# 2_adc.net
KiCad netlist of a schematic drawn in EAGLE
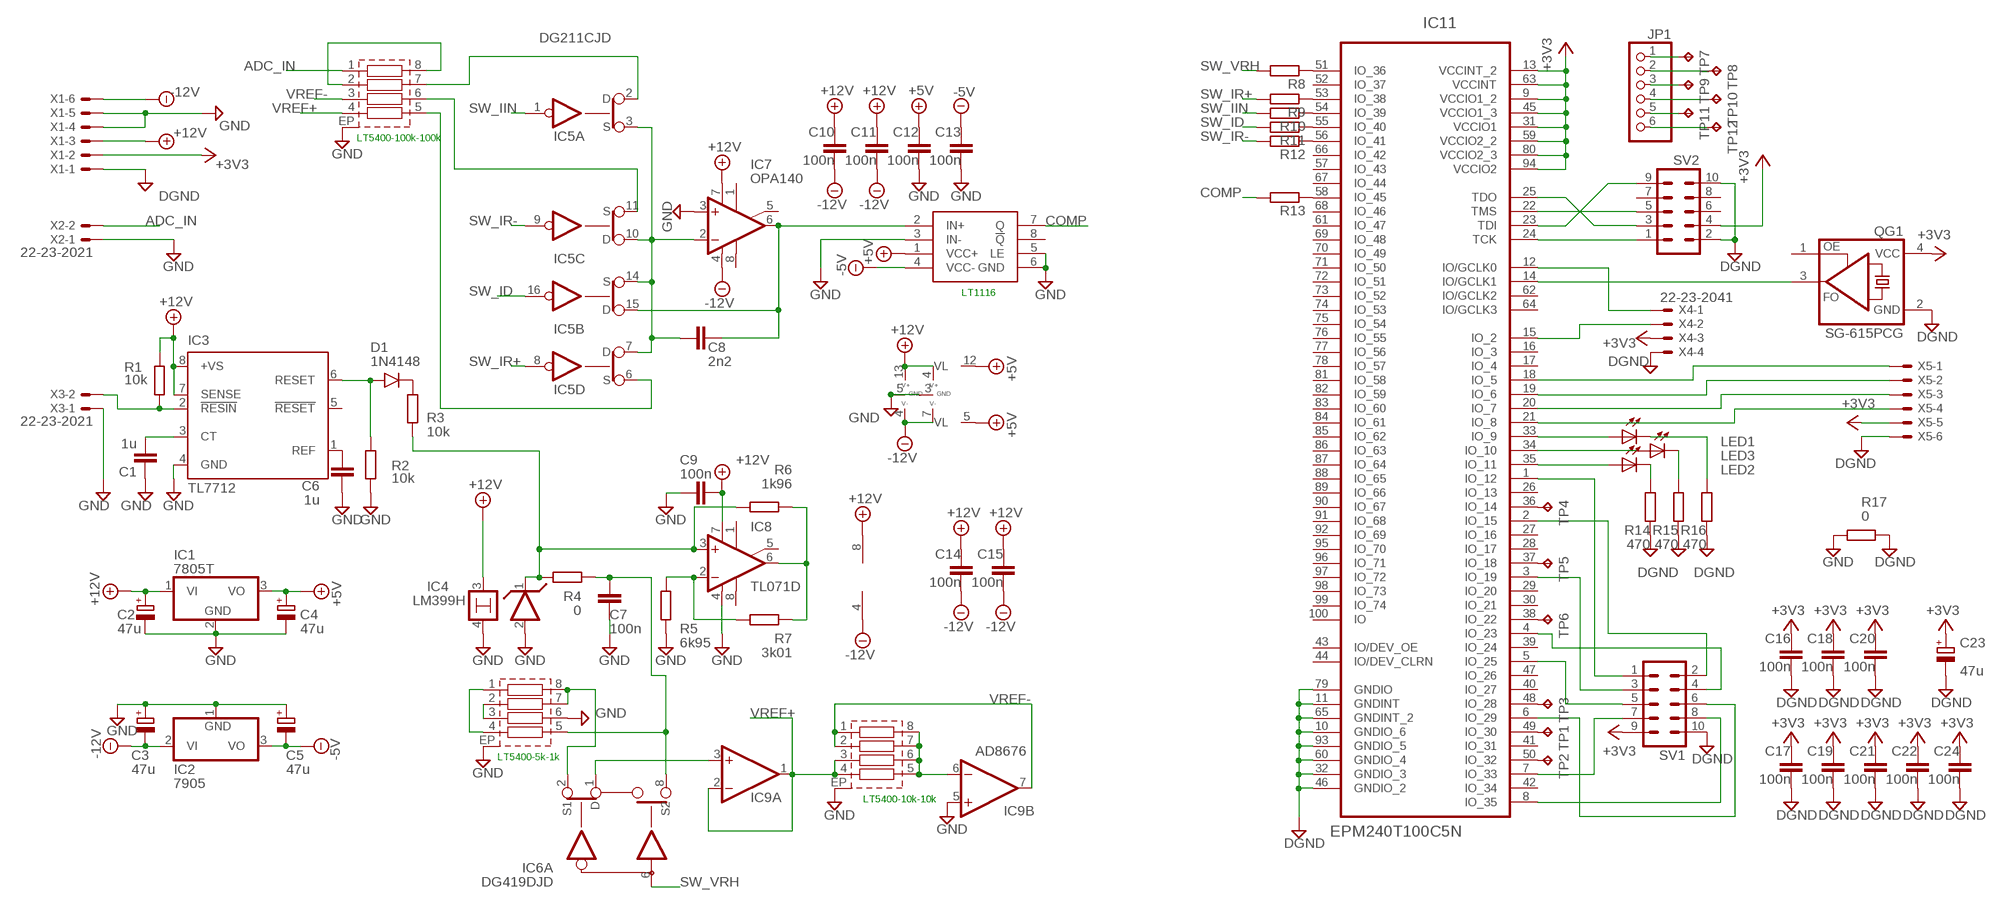
[diagram p0: schematic, sheet 1]

(export (version "E")
  (design (tool "Eeschema 10.0.6"))
  (components
    (comp (ref "C1")
      (value "1u")
      (footprint "eagle-import:R0805")
      (libsource (lib "eagle-import") (part "C_0806"))
    )
    (comp (ref "C2")
      (value "47u")
      (footprint "eagle-import:SMC_C")
      (libsource (lib "eagle-import") (part "CPOL-EUSMCC"))
    )
    (comp (ref "C3")
      (value "47u")
      (footprint "eagle-import:SMC_C")
      (libsource (lib "eagle-import") (part "CPOL-EUSMCC"))
    )
    (comp (ref "C4")
      (value "47u")
      (footprint "eagle-import:SMC_C")
      (libsource (lib "eagle-import") (part "CPOL-EUSMCC"))
    )
    (comp (ref "C5")
      (value "47u")
      (footprint "eagle-import:SMC_C")
      (libsource (lib "eagle-import") (part "CPOL-EUSMCC"))
    )
    (comp (ref "C6")
      (value "1u")
      (footprint "eagle-import:R0805")
      (libsource (lib "eagle-import") (part "C_0806"))
    )
    (comp (ref "C7")
      (value "100n")
      (footprint "eagle-import:C050-035X075")
      (libsource (lib "eagle-import") (part "C-EU050-035X075"))
    )
    (comp (ref "C8")
      (value "2n2")
      (footprint "eagle-import:C150-054X183")
      (libsource (lib "eagle-import") (part "C-EU150-054X183"))
    )
    (comp (ref "C9")
      (value "100n")
      (footprint "eagle-import:R0805")
      (libsource (lib "eagle-import") (part "C_0806"))
    )
    (comp (ref "C10")
      (value "100n")
      (footprint "eagle-import:R0805")
      (libsource (lib "eagle-import") (part "C_0806"))
    )
    (comp (ref "C11")
      (value "100n")
      (footprint "eagle-import:R0805")
      (libsource (lib "eagle-import") (part "C_0806"))
    )
    (comp (ref "C12")
      (value "100n")
      (footprint "eagle-import:R0805")
      (libsource (lib "eagle-import") (part "C_0806"))
    )
    (comp (ref "C13")
      (value "100n")
      (footprint "eagle-import:R0805")
      (libsource (lib "eagle-import") (part "C_0806"))
    )
    (comp (ref "C14")
      (value "100n")
      (footprint "eagle-import:R0805")
      (libsource (lib "eagle-import") (part "C_0806"))
    )
    (comp (ref "C15")
      (value "100n")
      (footprint "eagle-import:R0805")
      (libsource (lib "eagle-import") (part "C_0806"))
    )
    (comp (ref "C16")
      (value "100n")
      (footprint "eagle-import:R0805")
      (libsource (lib "eagle-import") (part "C_0806"))
    )
    (comp (ref "C17")
      (value "100n")
      (footprint "eagle-import:R0805")
      (libsource (lib "eagle-import") (part "C_0806"))
    )
    (comp (ref "C18")
      (value "100n")
      (footprint "eagle-import:R0805")
      (libsource (lib "eagle-import") (part "C_0806"))
    )
    (comp (ref "C19")
      (value "100n")
      (footprint "eagle-import:R0805")
      (libsource (lib "eagle-import") (part "C_0806"))
    )
    (comp (ref "C20")
      (value "100n")
      (footprint "eagle-import:R0805")
      (libsource (lib "eagle-import") (part "C_0806"))
    )
    (comp (ref "C21")
      (value "100n")
      (footprint "eagle-import:R0805")
      (libsource (lib "eagle-import") (part "C_0806"))
    )
    (comp (ref "C22")
      (value "100n")
      (footprint "eagle-import:R0805")
      (libsource (lib "eagle-import") (part "C_0806"))
    )
    (comp (ref "C23")
      (value "47u")
      (footprint "eagle-import:SMC_C")
      (libsource (lib "eagle-import") (part "CPOL-EUSMCC"))
    )
    (comp (ref "C24")
      (value "100n")
      (footprint "eagle-import:R0805")
      (libsource (lib "eagle-import") (part "C_0806"))
    )
    (comp (ref "D1")
      (value "1N4148")
      (footprint "eagle-import:SOD-80")
      (libsource (lib "eagle-import") (part "1N4148SOD"))
    )
    (comp (ref "IC1")
      (value "7805T")
      (footprint "eagle-import:TO220H")
      (libsource (lib "eagle-import") (part "78T05"))
    )
    (comp (ref "IC2")
      (value "7905")
      (footprint "eagle-import:TO220H")
      (libsource (lib "eagle-import") (part "79T05"))
    )
    (comp (ref "IC3")
      (value "TL7712")
      (footprint "eagle-import:SO08")
      (libsource (lib "eagle-import") (part "TL770D05AI"))
    )
    (comp (ref "IC4")
      (value "LM399H")
      (footprint "eagle-import:TO39_4")
      (libsource (lib "eagle-import") (part "LM399H"))
    )
    (comp (ref "IC5")
      (value "DG211CJD")
      (footprint "eagle-import:SO16")
      (libsource (lib "eagle-import") (part "DG211CJD"))
    )
    (comp (ref "IC6")
      (value "DG419DJD")
      (footprint "eagle-import:SO08")
      (libsource (lib "eagle-import") (part "DG419DJD"))
    )
    (comp (ref "IC7")
      (value "OPA140")
      (footprint "eagle-import:SO08")
      (libsource (lib "eagle-import") (part "TL071D"))
    )
    (comp (ref "IC8")
      (value "TL071D")
      (footprint "eagle-import:SO08")
      (libsource (lib "eagle-import") (part "TL071D"))
    )
    (comp (ref "IC9")
      (value "AD8676")
      (footprint "eagle-import:SO08")
      (libsource (lib "eagle-import") (part "TL072D"))
    )
    (comp (ref "IC10")
      (value "LT1116")
      (footprint "eagle-import:SO-08")
      (libsource (lib "eagle-import") (part "LT1116"))
    )
    (comp (ref "IC11")
      (value "EPM240T100C5N")
      (footprint "eagle-import:QFP50P1600X1600X120-100N")
      (libsource (lib "eagle-import") (part "EPM240T100C5N"))
    )
    (comp (ref "JP1")
      (value "PINHD-1X06_2.54")
      (footprint "eagle-import:1X06")
      (libsource (lib "eagle-import") (part "PINHD-1X06_2.54"))
    )
    (comp (ref "LED1")
      (value "LEDCHIPLED_0805")
      (footprint "eagle-import:CHIPLED_0805")
      (libsource (lib "eagle-import") (part "LEDCHIPLED_0805"))
    )
    (comp (ref "LED2")
      (value "LEDCHIPLED_0805")
      (footprint "eagle-import:CHIPLED_0805")
      (libsource (lib "eagle-import") (part "LEDCHIPLED_0805"))
    )
    (comp (ref "LED3")
      (value "LEDCHIPLED_0805")
      (footprint "eagle-import:CHIPLED_0805")
      (libsource (lib "eagle-import") (part "LEDCHIPLED_0805"))
    )
    (comp (ref "QG1")
      (value "SG-615PCG")
      (footprint "eagle-import:SG-615")
      (libsource (lib "eagle-import") (part "SG-615PCG"))
    )
    (comp (ref "R1")
      (value "10k")
      (footprint "eagle-import:R0805")
      (libsource (lib "eagle-import") (part "R_0805"))
    )
    (comp (ref "R2")
      (value "10k")
      (footprint "eagle-import:R0805")
      (libsource (lib "eagle-import") (part "R_0805"))
    )
    (comp (ref "R3")
      (value "10k")
      (footprint "eagle-import:R0805")
      (libsource (lib "eagle-import") (part "R_0805"))
    )
    (comp (ref "R4")
      (value "0")
      (footprint "eagle-import:R_TR191")
      (libsource (lib "eagle-import") (part "R191"))
    )
    (comp (ref "R5")
      (value "6k95")
      (footprint "eagle-import:R_TR191")
      (libsource (lib "eagle-import") (part "R191"))
    )
    (comp (ref "R6")
      (value "1k96")
      (footprint "eagle-import:R_TR191")
      (libsource (lib "eagle-import") (part "R191"))
    )
    (comp (ref "R7")
      (value "3k01")
      (footprint "eagle-import:R_TR191")
      (libsource (lib "eagle-import") (part "R191"))
    )
    (comp (ref "R8")
      (value "R_0805")
      (footprint "eagle-import:R0805")
      (libsource (lib "eagle-import") (part "R_0805"))
    )
    (comp (ref "R9")
      (value "R_0805")
      (footprint "eagle-import:R0805")
      (libsource (lib "eagle-import") (part "R_0805"))
    )
    (comp (ref "R10")
      (value "R_0805")
      (footprint "eagle-import:R0805")
      (libsource (lib "eagle-import") (part "R_0805"))
    )
    (comp (ref "R11")
      (value "R_0805")
      (footprint "eagle-import:R0805")
      (libsource (lib "eagle-import") (part "R_0805"))
    )
    (comp (ref "R12")
      (value "R_0805")
      (footprint "eagle-import:R0805")
      (libsource (lib "eagle-import") (part "R_0805"))
    )
    (comp (ref "R13")
      (value "R_0805")
      (footprint "eagle-import:R0805")
      (libsource (lib "eagle-import") (part "R_0805"))
    )
    (comp (ref "R14")
      (value "470")
      (footprint "eagle-import:R0805")
      (libsource (lib "eagle-import") (part "R_0805"))
    )
    (comp (ref "R15")
      (value "470")
      (footprint "eagle-import:R0805")
      (libsource (lib "eagle-import") (part "R_0805"))
    )
    (comp (ref "R16")
      (value "470")
      (footprint "eagle-import:R0805")
      (libsource (lib "eagle-import") (part "R_0805"))
    )
    (comp (ref "R17")
      (value "0")
      (footprint "eagle-import:R0805")
      (libsource (lib "eagle-import") (part "R_0805"))
    )
    (comp (ref "SV1")
      (value "ML10")
      (footprint "eagle-import:ML10")
      (libsource (lib "eagle-import") (part "ML10"))
    )
    (comp (ref "SV2")
      (value "ML10")
      (footprint "eagle-import:ML10")
      (libsource (lib "eagle-import") (part "ML10"))
    )
    (comp (ref "TP1")
      (value "TPB1,27")
      (footprint "eagle-import:B1,27")
      (libsource (lib "eagle-import") (part "TPB1,27"))
    )
    (comp (ref "TP2")
      (value "TPB1,27")
      (footprint "eagle-import:B1,27")
      (libsource (lib "eagle-import") (part "TPB1,27"))
    )
    (comp (ref "TP3")
      (value "TPB1,27")
      (footprint "eagle-import:B1,27")
      (libsource (lib "eagle-import") (part "TPB1,27"))
    )
    (comp (ref "TP4")
      (value "TPB1,27")
      (footprint "eagle-import:B1,27")
      (libsource (lib "eagle-import") (part "TPB1,27"))
    )
    (comp (ref "TP5")
      (value "TPB1,27")
      (footprint "eagle-import:B1,27")
      (libsource (lib "eagle-import") (part "TPB1,27"))
    )
    (comp (ref "TP6")
      (value "TPB1,27")
      (footprint "eagle-import:B1,27")
      (libsource (lib "eagle-import") (part "TPB1,27"))
    )
    (comp (ref "TP7")
      (value "TPB1,27")
      (footprint "eagle-import:B1,27")
      (libsource (lib "eagle-import") (part "TPB1,27"))
    )
    (comp (ref "TP8")
      (value "TPB1,27")
      (footprint "eagle-import:B1,27")
      (libsource (lib "eagle-import") (part "TPB1,27"))
    )
    (comp (ref "TP9")
      (value "TPB1,27")
      (footprint "eagle-import:B1,27")
      (libsource (lib "eagle-import") (part "TPB1,27"))
    )
    (comp (ref "TP10")
      (value "TPB1,27")
      (footprint "eagle-import:B1,27")
      (libsource (lib "eagle-import") (part "TPB1,27"))
    )
    (comp (ref "TP11")
      (value "TPB1,27")
      (footprint "eagle-import:B1,27")
      (libsource (lib "eagle-import") (part "TPB1,27"))
    )
    (comp (ref "TP12")
      (value "TPB1,27")
      (footprint "eagle-import:B1,27")
      (libsource (lib "eagle-import") (part "TPB1,27"))
    )
    (comp (ref "U$1")
      (value "LT5400-100k-100k")
      (footprint "eagle-import:MSOP8-EP")
      (libsource (lib "eagle-import") (part "LT5400"))
    )
    (comp (ref "U$2")
      (value "LT5400-5k-1k")
      (footprint "eagle-import:MSOP8-EP")
      (libsource (lib "eagle-import") (part "LT5400"))
    )
    (comp (ref "U$3")
      (value "LT5400-10k+10k")
      (footprint "eagle-import:MSOP8-EP")
      (libsource (lib "eagle-import") (part "LT5400"))
    )
    (comp (ref "X1")
      (value "22-23-2061")
      (footprint "eagle-import:22-23-2061")
      (fields (field (name "MF") "MOLEX"))
      (libsource (lib "eagle-import") (part "22-23-2061"))
    )
    (comp (ref "X2")
      (value "22-23-2021")
      (footprint "eagle-import:22-23-2021")
      (fields (field (name "MF") "MOLEX"))
      (libsource (lib "eagle-import") (part "22-23-2021"))
    )
    (comp (ref "X3")
      (value "22-23-2021")
      (footprint "eagle-import:22-23-2021")
      (fields (field (name "MF") "MOLEX"))
      (libsource (lib "eagle-import") (part "22-23-2021"))
    )
    (comp (ref "X4")
      (value "22-23-2041")
      (footprint "eagle-import:22-23-2041")
      (fields (field (name "MF") "MOLEX"))
      (libsource (lib "eagle-import") (part "22-23-2041"))
    )
    (comp (ref "X5")
      (value "22-23-2061")
      (footprint "eagle-import:22-23-2061")
      (fields (field (name "MF") "MOLEX"))
      (libsource (lib "eagle-import") (part "22-23-2061"))
    )
  )
  (nets
    (net (code "1") (name "+3V3") (class "Default")
      (node (ref "C16") (pin "2") (pinfunction "2_2") (pintype "passive"))
      (node (ref "C17") (pin "2") (pinfunction "2_2") (pintype "passive"))
      (node (ref "C18") (pin "2") (pinfunction "2_2") (pintype "passive"))
      (node (ref "C19") (pin "2") (pinfunction "2_2") (pintype "passive"))
      (node (ref "C20") (pin "2") (pinfunction "2_2") (pintype "passive"))
      (node (ref "C21") (pin "2") (pinfunction "2_2") (pintype "passive"))
      (node (ref "C22") (pin "2") (pinfunction "2_2") (pintype "passive"))
      (node (ref "C23") (pin "+") (pinfunction "+_+") (pintype "passive"))
      (node (ref "C24") (pin "2") (pinfunction "2_2") (pintype "passive"))
      (node (ref "IC11") (pin "13") (pinfunction "VCCINT_2_13") (pintype "power_in"))
      (node (ref "IC11") (pin "31") (pinfunction "VCCIO1_31") (pintype "power_in"))
      (node (ref "IC11") (pin "45") (pinfunction "VCCIO1_3_45") (pintype "power_in"))
      (node (ref "IC11") (pin "59") (pinfunction "VCCIO2_2_59") (pintype "power_in"))
      (node (ref "IC11") (pin "63") (pinfunction "VCCINT_63") (pintype "power_in"))
      (node (ref "IC11") (pin "80") (pinfunction "VCCIO2_3_80") (pintype "power_in"))
      (node (ref "IC11") (pin "9") (pinfunction "VCCIO1_2_9") (pintype "power_in"))
      (node (ref "IC11") (pin "94") (pinfunction "VCCIO2_94") (pintype "power_in"))
      (node (ref "QG1") (pin "4") (pinfunction "VCC_4") (pintype "power_in"))
      (node (ref "SV1") (pin "9") (pinfunction "9_9") (pintype "passive"))
      (node (ref "SV2") (pin "4") (pinfunction "4_4") (pintype "passive"))
      (node (ref "X1") (pin "2") (pinfunction "S_2") (pintype "passive"))
      (node (ref "X4") (pin "3") (pinfunction "S_3") (pintype "passive"))
      (node (ref "X5") (pin "5") (pinfunction "S_5") (pintype "passive"))
    )
    (net (code "2") (name "+5V") (class "Default")
      (node (ref "C12") (pin "2") (pinfunction "2_2") (pintype "passive"))
      (node (ref "C4") (pin "+") (pinfunction "+_+") (pintype "passive"))
      (node (ref "IC1") (pin "3") (pinfunction "VO_3") (pintype "passive"))
      (node (ref "IC10") (pin "1") (pinfunction "VCC+_1") (pintype "bidirectional"))
      (node (ref "IC5") (pin "12") (pinfunction "VL_12") (pintype "input"))
      (node (ref "IC6") (pin "5") (pinfunction "VL_5") (pintype "input"))
    )
    (net (code "3") (name "+12V") (class "Default")
      (node (ref "C10") (pin "2") (pinfunction "2_2") (pintype "passive"))
      (node (ref "C11") (pin "2") (pinfunction "2_2") (pintype "passive"))
      (node (ref "C14") (pin "2") (pinfunction "2_2") (pintype "passive"))
      (node (ref "C15") (pin "2") (pinfunction "2_2") (pintype "passive"))
      (node (ref "C2") (pin "+") (pinfunction "+_+") (pintype "passive"))
      (node (ref "C9") (pin "2") (pinfunction "2_2") (pintype "passive"))
      (node (ref "IC1") (pin "1") (pinfunction "VI_1") (pintype "input"))
      (node (ref "IC3") (pin "7") (pinfunction "SENSE_7") (pintype "input"))
      (node (ref "IC3") (pin "8") (pinfunction "+VS_8") (pintype "input"))
      (node (ref "IC4") (pin "3") (pinfunction "3_3") (pintype "input"))
      (node (ref "IC5") (pin "13") (pinfunction "V+_13") (pintype "power_in"))
      (node (ref "IC6") (pin "4") (pinfunction "V+_4") (pintype "power_in"))
      (node (ref "IC7") (pin "7") (pinfunction "V+_7") (pintype "power_in"))
      (node (ref "IC8") (pin "7") (pinfunction "V+_7") (pintype "power_in"))
      (node (ref "IC9") (pin "8") (pinfunction "V+_8") (pintype "power_in"))
      (node (ref "R1") (pin "2") (pinfunction "2_2") (pintype "passive"))
      (node (ref "X1") (pin "3") (pinfunction "S_3") (pintype "passive"))
    )
    (net (code "4") (name "-5V") (class "Default")
      (node (ref "C13") (pin "2") (pinfunction "2_2") (pintype "passive"))
      (node (ref "C5") (pin "-") (pinfunction "-_-") (pintype "passive"))
      (node (ref "IC10") (pin "4") (pinfunction "VCC-_4") (pintype "bidirectional"))
      (node (ref "IC2") (pin "3") (pinfunction "VO_3") (pintype "passive"))
    )
    (net (code "5") (name "-12V") (class "Default")
      (node (ref "C10") (pin "1") (pinfunction "1_1") (pintype "passive"))
      (node (ref "C11") (pin "1") (pinfunction "1_1") (pintype "passive"))
      (node (ref "C14") (pin "1") (pinfunction "1_1") (pintype "passive"))
      (node (ref "C15") (pin "1") (pinfunction "1_1") (pintype "passive"))
      (node (ref "C3") (pin "-") (pinfunction "-_-") (pintype "passive"))
      (node (ref "IC2") (pin "2") (pinfunction "VI_2") (pintype "input"))
      (node (ref "IC5") (pin "4") (pinfunction "V-_4") (pintype "power_in"))
      (node (ref "IC6") (pin "7") (pinfunction "V-_7") (pintype "power_in"))
      (node (ref "IC7") (pin "4") (pinfunction "V-_4") (pintype "power_in"))
      (node (ref "IC9") (pin "4") (pinfunction "V-_4") (pintype "power_in"))
      (node (ref "X1") (pin "6") (pinfunction "S_6") (pintype "passive"))
    )
    (net (code "6") (name "/ADC_IN") (class "Default")
      (node (ref "U$1") (pin "1") (pinfunction "R1A_1") (pintype "bidirectional"))
      (node (ref "X2") (pin "2") (pinfunction "S_2") (pintype "passive"))
    )
    (net (code "7") (name "/COMP") (class "Default")
      (node (ref "IC10") (pin "7") (pinfunction "Q_7") (pintype "bidirectional"))
      (node (ref "R13") (pin "2") (pinfunction "2_2") (pintype "passive"))
    )
    (net (code "8") (name "/SW_ID") (class "Default")
      (node (ref "IC5") (pin "16") (pinfunction "IN_16") (pintype "input"))
      (node (ref "R11") (pin "2") (pinfunction "2_2") (pintype "passive"))
    )
    (net (code "9") (name "/SW_IIN") (class "Default")
      (node (ref "IC5") (pin "1") (pinfunction "IN_1") (pintype "input"))
      (node (ref "R10") (pin "2") (pinfunction "2_2") (pintype "passive"))
    )
    (net (code "10") (name "/SW_IR+") (class "Default")
      (node (ref "IC5") (pin "8") (pinfunction "IN_8") (pintype "input"))
      (node (ref "R9") (pin "2") (pinfunction "2_2") (pintype "passive"))
    )
    (net (code "11") (name "/SW_IR-") (class "Default")
      (node (ref "IC5") (pin "9") (pinfunction "IN_9") (pintype "input"))
      (node (ref "R12") (pin "2") (pinfunction "2_2") (pintype "passive"))
    )
    (net (code "12") (name "/SW_VRH") (class "Default")
      (node (ref "IC6") (pin "6") (pinfunction "IN_6") (pintype "input"))
      (node (ref "R8") (pin "2") (pinfunction "2_2") (pintype "passive"))
    )
    (net (code "13") (name "/VREF+") (class "Default")
      (node (ref "IC9") (pin "1") (pinfunction "OUT_1") (pintype "output"))
      (node (ref "IC9") (pin "2") (pinfunction "-IN_2") (pintype "input"))
      (node (ref "U$1") (pin "4") (pinfunction "R4A_4") (pintype "bidirectional"))
      (node (ref "U$3") (pin "3") (pinfunction "R3A_3") (pintype "bidirectional"))
      (node (ref "U$3") (pin "4") (pinfunction "R4A_4") (pintype "bidirectional"))
    )
    (net (code "14") (name "/VREF-") (class "Default")
      (node (ref "IC9") (pin "7") (pinfunction "OUT_7") (pintype "output"))
      (node (ref "U$1") (pin "3") (pinfunction "R3A_3") (pintype "bidirectional"))
      (node (ref "U$3") (pin "1") (pinfunction "R1A_1") (pintype "bidirectional"))
      (node (ref "U$3") (pin "2") (pinfunction "R2A_2") (pintype "bidirectional"))
    )
    (net (code "15") (name "DGND") (class "Default")
      (node (ref "C16") (pin "1") (pinfunction "1_1") (pintype "passive"))
      (node (ref "C17") (pin "1") (pinfunction "1_1") (pintype "passive"))
      (node (ref "C18") (pin "1") (pinfunction "1_1") (pintype "passive"))
      (node (ref "C19") (pin "1") (pinfunction "1_1") (pintype "passive"))
      (node (ref "C20") (pin "1") (pinfunction "1_1") (pintype "passive"))
      (node (ref "C21") (pin "1") (pinfunction "1_1") (pintype "passive"))
      (node (ref "C22") (pin "1") (pinfunction "1_1") (pintype "passive"))
      (node (ref "C23") (pin "-") (pinfunction "-_-") (pintype "passive"))
      (node (ref "C24") (pin "1") (pinfunction "1_1") (pintype "passive"))
      (node (ref "IC11") (pin "10") (pinfunction "GNDIO_6_10") (pintype "passive"))
      (node (ref "IC11") (pin "11") (pinfunction "GNDINT_11") (pintype "passive"))
      (node (ref "IC11") (pin "32") (pinfunction "GNDIO_3_32") (pintype "passive"))
      (node (ref "IC11") (pin "46") (pinfunction "GNDIO_2_46") (pintype "passive"))
      (node (ref "IC11") (pin "60") (pinfunction "GNDIO_4_60") (pintype "passive"))
      (node (ref "IC11") (pin "65") (pinfunction "GNDINT_2_65") (pintype "passive"))
      (node (ref "IC11") (pin "79") (pinfunction "GNDIO_79") (pintype "passive"))
      (node (ref "IC11") (pin "93") (pinfunction "GNDIO_5_93") (pintype "passive"))
      (node (ref "QG1") (pin "2") (pinfunction "GND_2") (pintype "power_in"))
      (node (ref "R14") (pin "2") (pinfunction "2_2") (pintype "passive"))
      (node (ref "R15") (pin "2") (pinfunction "2_2") (pintype "passive"))
      (node (ref "R16") (pin "2") (pinfunction "2_2") (pintype "passive"))
      (node (ref "R17") (pin "2") (pinfunction "2_2") (pintype "passive"))
      (node (ref "SV1") (pin "10") (pinfunction "10_10") (pintype "passive"))
      (node (ref "SV2") (pin "10") (pinfunction "10_10") (pintype "passive"))
      (node (ref "SV2") (pin "2") (pinfunction "2_2") (pintype "passive"))
      (node (ref "X1") (pin "1") (pinfunction "S_1") (pintype "passive"))
      (node (ref "X4") (pin "4") (pinfunction "S_4") (pintype "passive"))
      (node (ref "X5") (pin "6") (pinfunction "S_6") (pintype "passive"))
    )
    (net (code "16") (name "GND") (class "Default")
      (node (ref "C1") (pin "1") (pinfunction "1_1") (pintype "passive"))
      (node (ref "C12") (pin "1") (pinfunction "1_1") (pintype "passive"))
      (node (ref "C13") (pin "1") (pinfunction "1_1") (pintype "passive"))
      (node (ref "C2") (pin "-") (pinfunction "-_-") (pintype "passive"))
      (node (ref "C3") (pin "+") (pinfunction "+_+") (pintype "passive"))
      (node (ref "C4") (pin "-") (pinfunction "-_-") (pintype "passive"))
      (node (ref "C5") (pin "+") (pinfunction "+_+") (pintype "passive"))
      (node (ref "C6") (pin "1") (pinfunction "1_1") (pintype "passive"))
      (node (ref "C7") (pin "2") (pinfunction "2_2") (pintype "passive"))
      (node (ref "C9") (pin "1") (pinfunction "1_1") (pintype "passive"))
      (node (ref "IC1") (pin "2") (pinfunction "GND_2") (pintype "passive"))
      (node (ref "IC10") (pin "3") (pinfunction "IN-_3") (pintype "bidirectional"))
      (node (ref "IC10") (pin "5") (pinfunction "LE_5") (pintype "bidirectional"))
      (node (ref "IC10") (pin "6") (pinfunction "GND_6") (pintype "bidirectional"))
      (node (ref "IC2") (pin "1") (pinfunction "GND_1") (pintype "passive"))
      (node (ref "IC3") (pin "4") (pinfunction "GND_4") (pintype "power_in"))
      (node (ref "IC4") (pin "2") (pinfunction "2_2") (pintype "input"))
      (node (ref "IC4") (pin "4") (pinfunction "4_4") (pintype "input"))
      (node (ref "IC5") (pin "5") (pinfunction "GND_5") (pintype "power_in"))
      (node (ref "IC6") (pin "3") (pinfunction "GND_3") (pintype "power_in"))
      (node (ref "IC7") (pin "3") (pinfunction "+IN_3") (pintype "input"))
      (node (ref "IC8") (pin "4") (pinfunction "V-_4") (pintype "power_in"))
      (node (ref "IC9") (pin "5") (pinfunction "+IN_5") (pintype "input"))
      (node (ref "R17") (pin "1") (pinfunction "1_1") (pintype "passive"))
      (node (ref "R2") (pin "1") (pinfunction "1_1") (pintype "passive"))
      (node (ref "R5") (pin "P$1") (pinfunction "1_P$1") (pintype "passive"))
      (node (ref "U$1") (pin "EP") (pinfunction "SH_EP") (pintype "bidirectional"))
      (node (ref "U$2") (pin "6") (pinfunction "R3B_6") (pintype "bidirectional"))
      (node (ref "U$2") (pin "EP") (pinfunction "SH_EP") (pintype "bidirectional"))
      (node (ref "U$3") (pin "EP") (pinfunction "SH_EP") (pintype "bidirectional"))
      (node (ref "X1") (pin "4") (pinfunction "S_4") (pintype "passive"))
      (node (ref "X1") (pin "5") (pinfunction "S_5") (pintype "passive"))
      (node (ref "X2") (pin "1") (pinfunction "S_1") (pintype "passive"))
      (node (ref "X3") (pin "1") (pinfunction "S_1") (pintype "passive"))
    )
    (net (code "17") (name "Net-(D1-PadK)") (class "Default")
      (node (ref "D1") (pin "K") (pinfunction "K_K") (pintype "output"))
      (node (ref "R3") (pin "2") (pinfunction "2_2") (pintype "passive"))
    )
    (net (code "18") (name "Net-(IC3-CT)") (class "Default")
      (node (ref "C1") (pin "2") (pinfunction "2_2") (pintype "passive"))
      (node (ref "IC3") (pin "3") (pinfunction "CT_3") (pintype "input"))
    )
    (net (code "19") (name "Net-(IC3-REF)") (class "Default")
      (node (ref "C6") (pin "2") (pinfunction "2_2") (pintype "passive"))
      (node (ref "IC3") (pin "1") (pinfunction "REF_1") (pintype "input"))
    )
    (net (code "20") (name "Net-(IC3-RESET)") (class "Default")
      (node (ref "D1") (pin "A") (pinfunction "A_A") (pintype "input"))
      (node (ref "IC3") (pin "6") (pinfunction "RESET_6") (pintype "open_collector"))
      (node (ref "R2") (pin "2") (pinfunction "2_2") (pintype "passive"))
    )
    (net (code "21") (name "Net-(IC3-~{RESIN})") (class "Default")
      (node (ref "IC3") (pin "2") (pinfunction "~{RESIN}_2") (pintype "input"))
      (node (ref "R1") (pin "1") (pinfunction "1_1") (pintype "passive"))
      (node (ref "X3") (pin "2") (pinfunction "S_2") (pintype "passive"))
    )
    (net (code "22") (name "Net-(IC5A-D)") (class "Default")
      (node (ref "IC5") (pin "2") (pinfunction "D_2") (pintype "bidirectional"))
      (node (ref "U$1") (pin "7") (pinfunction "R2B_7") (pintype "bidirectional"))
    )
    (net (code "23") (name "Net-(IC5A-S)") (class "Default")
      (node (ref "C8") (pin "1") (pinfunction "1_1") (pintype "passive"))
      (node (ref "IC5") (pin "10") (pinfunction "D_10") (pintype "bidirectional"))
      (node (ref "IC5") (pin "14") (pinfunction "S_14") (pintype "bidirectional"))
      (node (ref "IC5") (pin "3") (pinfunction "S_3") (pintype "bidirectional"))
      (node (ref "IC5") (pin "7") (pinfunction "D_7") (pintype "bidirectional"))
      (node (ref "IC7") (pin "2") (pinfunction "-IN_2") (pintype "input"))
    )
    (net (code "24") (name "Net-(IC5C-S)") (class "Default")
      (node (ref "IC5") (pin "11") (pinfunction "S_11") (pintype "bidirectional"))
      (node (ref "U$1") (pin "6") (pinfunction "R3B_6") (pintype "bidirectional"))
    )
    (net (code "25") (name "Net-(IC5D-S)") (class "Default")
      (node (ref "IC5") (pin "6") (pinfunction "S_6") (pintype "bidirectional"))
      (node (ref "U$1") (pin "5") (pinfunction "R4B_5") (pintype "bidirectional"))
    )
    (net (code "26") (name "Net-(IC6A-D)") (class "Default")
      (node (ref "IC6") (pin "1") (pinfunction "D_1") (pintype "bidirectional"))
      (node (ref "IC9") (pin "3") (pinfunction "+IN_3") (pintype "input"))
    )
    (net (code "27") (name "Net-(IC6A-S1)") (class "Default")
      (node (ref "IC6") (pin "2") (pinfunction "S1_2") (pintype "bidirectional"))
      (node (ref "U$2") (pin "7") (pinfunction "R2B_7") (pintype "bidirectional"))
      (node (ref "U$2") (pin "8") (pinfunction "R1B_8") (pintype "bidirectional"))
    )
    (net (code "28") (name "Net-(IC6A-S2)") (class "Default")
      (node (ref "C7") (pin "1") (pinfunction "1_1") (pintype "passive"))
      (node (ref "IC6") (pin "8") (pinfunction "S2_8") (pintype "bidirectional"))
      (node (ref "R4") (pin "P$1") (pinfunction "1_P$1") (pintype "passive"))
      (node (ref "U$2") (pin "5") (pinfunction "R4B_5") (pintype "bidirectional"))
    )
    (net (code "29") (name "Net-(IC8-+IN)") (class "Default")
      (node (ref "IC4") (pin "1") (pinfunction "1_1") (pintype "input"))
      (node (ref "IC8") (pin "3") (pinfunction "+IN_3") (pintype "input"))
      (node (ref "R3") (pin "1") (pinfunction "1_1") (pintype "passive"))
      (node (ref "R4") (pin "P$2") (pinfunction "2_P$2") (pintype "passive"))
      (node (ref "R6") (pin "P$2") (pinfunction "2_P$2") (pintype "passive"))
    )
    (net (code "30") (name "Net-(IC8--IN)") (class "Default")
      (node (ref "IC8") (pin "2") (pinfunction "-IN_2") (pintype "input"))
      (node (ref "R5") (pin "P$2") (pinfunction "2_P$2") (pintype "passive"))
      (node (ref "R7") (pin "P$2") (pinfunction "2_P$2") (pintype "passive"))
    )
    (net (code "31") (name "Net-(IC8-OUT)") (class "Default")
      (node (ref "IC8") (pin "6") (pinfunction "OUT_6") (pintype "output"))
      (node (ref "R6") (pin "P$1") (pinfunction "1_P$1") (pintype "passive"))
      (node (ref "R7") (pin "P$1") (pinfunction "1_P$1") (pintype "passive"))
    )
    (net (code "32") (name "Net-(IC9B--IN)") (class "Default")
      (node (ref "IC9") (pin "6") (pinfunction "-IN_6") (pintype "input"))
      (node (ref "U$3") (pin "5") (pinfunction "R4B_5") (pintype "bidirectional"))
      (node (ref "U$3") (pin "6") (pinfunction "R3B_6") (pintype "bidirectional"))
      (node (ref "U$3") (pin "7") (pinfunction "R2B_7") (pintype "bidirectional"))
      (node (ref "U$3") (pin "8") (pinfunction "R1B_8") (pintype "bidirectional"))
    )
    (net (code "33") (name "Net-(IC10-IN+)") (class "Default")
      (node (ref "C8") (pin "2") (pinfunction "2_2") (pintype "passive"))
      (node (ref "IC10") (pin "2") (pinfunction "IN+_2") (pintype "bidirectional"))
      (node (ref "IC5") (pin "15") (pinfunction "D_15") (pintype "bidirectional"))
      (node (ref "IC7") (pin "6") (pinfunction "OUT_6") (pintype "output"))
    )
    (net (code "34") (name "Net-(IC11-IO_2)") (class "Default")
      (node (ref "IC11") (pin "15") (pinfunction "IO_2_15") (pintype "bidirectional"))
      (node (ref "X4") (pin "2") (pinfunction "S_2") (pintype "passive"))
    )
    (net (code "35") (name "Net-(IC11-IO_5)") (class "Default")
      (node (ref "IC11") (pin "18") (pinfunction "IO_5_18") (pintype "bidirectional"))
      (node (ref "X5") (pin "1") (pinfunction "S_1") (pintype "passive"))
    )
    (net (code "36") (name "Net-(IC11-IO_6)") (class "Default")
      (node (ref "IC11") (pin "19") (pinfunction "IO_6_19") (pintype "bidirectional"))
      (node (ref "X5") (pin "2") (pinfunction "S_2") (pintype "passive"))
    )
    (net (code "37") (name "Net-(IC11-IO_7)") (class "Default")
      (node (ref "IC11") (pin "20") (pinfunction "IO_7_20") (pintype "bidirectional"))
      (node (ref "X5") (pin "3") (pinfunction "S_3") (pintype "passive"))
    )
    (net (code "38") (name "Net-(IC11-IO_8)") (class "Default")
      (node (ref "IC11") (pin "21") (pinfunction "IO_8_21") (pintype "bidirectional"))
      (node (ref "X5") (pin "4") (pinfunction "S_4") (pintype "passive"))
    )
    (net (code "39") (name "Net-(IC11-IO_9)") (class "Default")
      (node (ref "IC11") (pin "33") (pinfunction "IO_9_33") (pintype "bidirectional"))
      (node (ref "LED1") (pin "A") (pinfunction "A_A") (pintype "passive"))
    )
    (net (code "40") (name "Net-(IC11-IO_10)") (class "Default")
      (node (ref "IC11") (pin "34") (pinfunction "IO_10_34") (pintype "bidirectional"))
      (node (ref "LED3") (pin "A") (pinfunction "A_A") (pintype "passive"))
    )
    (net (code "41") (name "Net-(IC11-IO_11)") (class "Default")
      (node (ref "IC11") (pin "35") (pinfunction "IO_11_35") (pintype "bidirectional"))
      (node (ref "LED2") (pin "A") (pinfunction "A_A") (pintype "passive"))
    )
    (net (code "42") (name "Net-(IC11-IO_12)") (class "Default")
      (node (ref "IC11") (pin "1") (pinfunction "IO_12_1") (pintype "bidirectional"))
      (node (ref "SV1") (pin "1") (pinfunction "1_1") (pintype "passive"))
    )
    (net (code "43") (name "Net-(IC11-IO_14)") (class "Default")
      (node (ref "IC11") (pin "36") (pinfunction "IO_14_36") (pintype "bidirectional"))
      (node (ref "TP4") (pin "TP") (pinfunction "TP_TP") (pintype "input"))
    )
    (net (code "44") (name "Net-(IC11-IO_15)") (class "Default")
      (node (ref "IC11") (pin "2") (pinfunction "IO_15_2") (pintype "bidirectional"))
      (node (ref "SV1") (pin "2") (pinfunction "2_2") (pintype "passive"))
    )
    (net (code "45") (name "Net-(IC11-IO_18)") (class "Default")
      (node (ref "IC11") (pin "37") (pinfunction "IO_18_37") (pintype "bidirectional"))
      (node (ref "TP5") (pin "TP") (pinfunction "TP_TP") (pintype "input"))
    )
    (net (code "46") (name "Net-(IC11-IO_19)") (class "Default")
      (node (ref "IC11") (pin "3") (pinfunction "IO_19_3") (pintype "bidirectional"))
      (node (ref "SV1") (pin "3") (pinfunction "3_3") (pintype "passive"))
    )
    (net (code "47") (name "Net-(IC11-IO_22)") (class "Default")
      (node (ref "IC11") (pin "38") (pinfunction "IO_22_38") (pintype "bidirectional"))
      (node (ref "TP6") (pin "TP") (pinfunction "TP_TP") (pintype "input"))
    )
    (net (code "48") (name "Net-(IC11-IO_23)") (class "Default")
      (node (ref "IC11") (pin "4") (pinfunction "IO_23_4") (pintype "bidirectional"))
      (node (ref "SV1") (pin "4") (pinfunction "4_4") (pintype "passive"))
    )
    (net (code "49") (name "Net-(IC11-IO_25)") (class "Default")
      (node (ref "IC11") (pin "5") (pinfunction "IO_25_5") (pintype "bidirectional"))
      (node (ref "SV1") (pin "5") (pinfunction "5_5") (pintype "passive"))
    )
    (net (code "50") (name "Net-(IC11-IO_28)") (class "Default")
      (node (ref "IC11") (pin "48") (pinfunction "IO_28_48") (pintype "bidirectional"))
      (node (ref "TP3") (pin "TP") (pinfunction "TP_TP") (pintype "input"))
    )
    (net (code "51") (name "Net-(IC11-IO_29)") (class "Default")
      (node (ref "IC11") (pin "6") (pinfunction "IO_29_6") (pintype "bidirectional"))
      (node (ref "SV1") (pin "6") (pinfunction "6_6") (pintype "passive"))
    )
    (net (code "52") (name "Net-(IC11-IO_30)") (class "Default")
      (node (ref "IC11") (pin "49") (pinfunction "IO_30_49") (pintype "bidirectional"))
      (node (ref "TP1") (pin "TP") (pinfunction "TP_TP") (pintype "input"))
    )
    (net (code "53") (name "Net-(IC11-IO_32)") (class "Default")
      (node (ref "IC11") (pin "50") (pinfunction "IO_32_50") (pintype "bidirectional"))
      (node (ref "TP2") (pin "TP") (pinfunction "TP_TP") (pintype "input"))
    )
    (net (code "54") (name "Net-(IC11-IO_33)") (class "Default")
      (node (ref "IC11") (pin "7") (pinfunction "IO_33_7") (pintype "bidirectional"))
      (node (ref "SV1") (pin "7") (pinfunction "7_7") (pintype "passive"))
    )
    (net (code "55") (name "Net-(IC11-IO_35)") (class "Default")
      (node (ref "IC11") (pin "8") (pinfunction "IO_35_8") (pintype "bidirectional"))
      (node (ref "SV1") (pin "8") (pinfunction "8_8") (pintype "passive"))
    )
    (net (code "56") (name "Net-(IC11-IO_36)") (class "Default")
      (node (ref "IC11") (pin "51") (pinfunction "IO_36_51") (pintype "bidirectional"))
      (node (ref "R8") (pin "1") (pinfunction "1_1") (pintype "passive"))
    )
    (net (code "57") (name "Net-(IC11-IO_38)") (class "Default")
      (node (ref "IC11") (pin "53") (pinfunction "IO_38_53") (pintype "bidirectional"))
      (node (ref "R9") (pin "1") (pinfunction "1_1") (pintype "passive"))
    )
    (net (code "58") (name "Net-(IC11-IO_39)") (class "Default")
      (node (ref "IC11") (pin "54") (pinfunction "IO_39_54") (pintype "bidirectional"))
      (node (ref "R10") (pin "1") (pinfunction "1_1") (pintype "passive"))
    )
    (net (code "59") (name "Net-(IC11-IO_40)") (class "Default")
      (node (ref "IC11") (pin "55") (pinfunction "IO_40_55") (pintype "bidirectional"))
      (node (ref "R11") (pin "1") (pinfunction "1_1") (pintype "passive"))
    )
    (net (code "60") (name "Net-(IC11-IO_41)") (class "Default")
      (node (ref "IC11") (pin "56") (pinfunction "IO_41_56") (pintype "bidirectional"))
      (node (ref "R12") (pin "1") (pinfunction "1_1") (pintype "passive"))
    )
    (net (code "61") (name "Net-(IC11-IO_45)") (class "Default")
      (node (ref "IC11") (pin "58") (pinfunction "IO_45_58") (pintype "bidirectional"))
      (node (ref "R13") (pin "1") (pinfunction "1_1") (pintype "passive"))
    )
    (net (code "62") (name "Net-(IC11-IO{slash}GCLK0)") (class "Default")
      (node (ref "IC11") (pin "12") (pinfunction "IO/GCLK0_12") (pintype "bidirectional"))
      (node (ref "X4") (pin "1") (pinfunction "S_1") (pintype "passive"))
    )
    (net (code "63") (name "Net-(IC11-IO{slash}GCLK1)") (class "Default")
      (node (ref "IC11") (pin "14") (pinfunction "IO/GCLK1_14") (pintype "bidirectional"))
      (node (ref "QG1") (pin "3") (pinfunction "FO_3") (pintype "output"))
    )
    (net (code "64") (name "Net-(IC11-TCK)") (class "Default")
      (node (ref "IC11") (pin "24") (pinfunction "TCK_24") (pintype "input"))
      (node (ref "SV2") (pin "1") (pinfunction "1_1") (pintype "passive"))
    )
    (net (code "65") (name "Net-(IC11-TDI)") (class "Default")
      (node (ref "IC11") (pin "23") (pinfunction "TDI_23") (pintype "input"))
      (node (ref "SV2") (pin "9") (pinfunction "9_9") (pintype "passive"))
    )
    (net (code "66") (name "Net-(IC11-TDO)") (class "Default")
      (node (ref "IC11") (pin "25") (pinfunction "TDO_25") (pintype "output"))
      (node (ref "SV2") (pin "3") (pinfunction "3_3") (pintype "passive"))
    )
    (net (code "67") (name "Net-(IC11-TMS)") (class "Default")
      (node (ref "IC11") (pin "22") (pinfunction "TMS_22") (pintype "input"))
      (node (ref "SV2") (pin "5") (pinfunction "5_5") (pintype "passive"))
    )
    (net (code "68") (name "Net-(JP1-Pad1)") (class "Default")
      (node (ref "JP1") (pin "1") (pinfunction "1_1") (pintype "passive"))
      (node (ref "TP7") (pin "TP") (pinfunction "TP_TP") (pintype "input"))
    )
    (net (code "69") (name "Net-(JP1-Pad2)") (class "Default")
      (node (ref "JP1") (pin "2") (pinfunction "2_2") (pintype "passive"))
      (node (ref "TP8") (pin "TP") (pinfunction "TP_TP") (pintype "input"))
    )
    (net (code "70") (name "Net-(JP1-Pad3)") (class "Default")
      (node (ref "JP1") (pin "3") (pinfunction "3_3") (pintype "passive"))
      (node (ref "TP9") (pin "TP") (pinfunction "TP_TP") (pintype "input"))
    )
    (net (code "71") (name "Net-(JP1-Pad4)") (class "Default")
      (node (ref "JP1") (pin "4") (pinfunction "4_4") (pintype "passive"))
      (node (ref "TP10") (pin "TP") (pinfunction "TP_TP") (pintype "input"))
    )
    (net (code "72") (name "Net-(JP1-Pad5)") (class "Default")
      (node (ref "JP1") (pin "5") (pinfunction "5_5") (pintype "passive"))
      (node (ref "TP11") (pin "TP") (pinfunction "TP_TP") (pintype "input"))
    )
    (net (code "73") (name "Net-(JP1-Pad6)") (class "Default")
      (node (ref "JP1") (pin "6") (pinfunction "6_6") (pintype "passive"))
      (node (ref "TP12") (pin "TP") (pinfunction "TP_TP") (pintype "input"))
    )
    (net (code "74") (name "Net-(LED1-PadC)") (class "Default")
      (node (ref "LED1") (pin "C") (pinfunction "C_C") (pintype "passive"))
      (node (ref "R16") (pin "1") (pinfunction "1_1") (pintype "passive"))
    )
    (net (code "75") (name "Net-(LED2-PadC)") (class "Default")
      (node (ref "LED2") (pin "C") (pinfunction "C_C") (pintype "passive"))
      (node (ref "R14") (pin "1") (pinfunction "1_1") (pintype "passive"))
    )
    (net (code "76") (name "Net-(LED3-PadC)") (class "Default")
      (node (ref "LED3") (pin "C") (pinfunction "C_C") (pintype "passive"))
      (node (ref "R15") (pin "1") (pinfunction "1_1") (pintype "passive"))
    )
    (net (code "77") (name "Net-(U$1-R1B)") (class "Default")
      (node (ref "U$1") (pin "2") (pinfunction "R2A_2") (pintype "bidirectional"))
      (node (ref "U$1") (pin "8") (pinfunction "R1B_8") (pintype "bidirectional"))
    )
    (net (code "78") (name "Net-(U$2-R1A)") (class "Default")
      (node (ref "U$2") (pin "1") (pinfunction "R1A_1") (pintype "bidirectional"))
      (node (ref "U$2") (pin "4") (pinfunction "R4A_4") (pintype "bidirectional"))
    )
    (net (code "79") (name "Net-(U$2-R2A)") (class "Default")
      (node (ref "U$2") (pin "2") (pinfunction "R2A_2") (pintype "bidirectional"))
      (node (ref "U$2") (pin "3") (pinfunction "R3A_3") (pintype "bidirectional"))
    )
    (net (code "80") (name "unconnected-(IC3-~{RESET}-Pad5)") (class "Default")
      (node (ref "IC3") (pin "5") (pinfunction "~{RESET}_5") (pintype "open_collector"))
    )
    (net (code "81") (name "unconnected-(IC7-ON1-Pad1)") (class "Default")
      (node (ref "IC7") (pin "1") (pinfunction "ON1_1") (pintype "passive"))
    )
    (net (code "82") (name "unconnected-(IC7-ON2-Pad5)") (class "Default")
      (node (ref "IC7") (pin "5") (pinfunction "ON2_5") (pintype "passive"))
    )
    (net (code "83") (name "unconnected-(IC7-OPT-Pad8)") (class "Default")
      (node (ref "IC7") (pin "8") (pinfunction "OPT_8") (pintype "passive"))
    )
    (net (code "84") (name "unconnected-(IC8-ON1-Pad1)") (class "Default")
      (node (ref "IC8") (pin "1") (pinfunction "ON1_1") (pintype "passive"))
    )
    (net (code "85") (name "unconnected-(IC8-ON2-Pad5)") (class "Default")
      (node (ref "IC8") (pin "5") (pinfunction "ON2_5") (pintype "passive"))
    )
    (net (code "86") (name "unconnected-(IC8-OPT-Pad8)") (class "Default")
      (node (ref "IC8") (pin "8") (pinfunction "OPT_8") (pintype "passive"))
    )
    (net (code "87") (name "unconnected-(IC10-~{Q}-Pad8)") (class "Default")
      (node (ref "IC10") (pin "8") (pinfunction "~{Q}_8") (pintype "bidirectional"))
    )
    (net (code "88") (name "unconnected-(IC11-IO-Pad100)") (class "Default")
      (node (ref "IC11") (pin "100") (pinfunction "IO_100") (pintype "bidirectional"))
    )
    (net (code "89") (name "unconnected-(IC11-IO_3-Pad16)") (class "Default")
      (node (ref "IC11") (pin "16") (pinfunction "IO_3_16") (pintype "bidirectional"))
    )
    (net (code "90") (name "unconnected-(IC11-IO_4-Pad17)") (class "Default")
      (node (ref "IC11") (pin "17") (pinfunction "IO_4_17") (pintype "bidirectional"))
    )
    (net (code "91") (name "unconnected-(IC11-IO_13-Pad26)") (class "Default")
      (node (ref "IC11") (pin "26") (pinfunction "IO_13_26") (pintype "bidirectional"))
    )
    (net (code "92") (name "unconnected-(IC11-IO_16-Pad27)") (class "Default")
      (node (ref "IC11") (pin "27") (pinfunction "IO_16_27") (pintype "bidirectional"))
    )
    (net (code "93") (name "unconnected-(IC11-IO_17-Pad28)") (class "Default")
      (node (ref "IC11") (pin "28") (pinfunction "IO_17_28") (pintype "bidirectional"))
    )
    (net (code "94") (name "unconnected-(IC11-IO_20-Pad29)") (class "Default")
      (node (ref "IC11") (pin "29") (pinfunction "IO_20_29") (pintype "bidirectional"))
    )
    (net (code "95") (name "unconnected-(IC11-IO_21-Pad30)") (class "Default")
      (node (ref "IC11") (pin "30") (pinfunction "IO_21_30") (pintype "bidirectional"))
    )
    (net (code "96") (name "unconnected-(IC11-IO_24-Pad39)") (class "Default")
      (node (ref "IC11") (pin "39") (pinfunction "IO_24_39") (pintype "bidirectional"))
    )
    (net (code "97") (name "unconnected-(IC11-IO_26-Pad47)") (class "Default")
      (node (ref "IC11") (pin "47") (pinfunction "IO_26_47") (pintype "bidirectional"))
    )
    (net (code "98") (name "unconnected-(IC11-IO_27-Pad40)") (class "Default")
      (node (ref "IC11") (pin "40") (pinfunction "IO_27_40") (pintype "bidirectional"))
    )
    (net (code "99") (name "unconnected-(IC11-IO_31-Pad41)") (class "Default")
      (node (ref "IC11") (pin "41") (pinfunction "IO_31_41") (pintype "bidirectional"))
    )
    (net (code "100") (name "unconnected-(IC11-IO_34-Pad42)") (class "Default")
      (node (ref "IC11") (pin "42") (pinfunction "IO_34_42") (pintype "bidirectional"))
    )
    (net (code "101") (name "unconnected-(IC11-IO_37-Pad52)") (class "Default")
      (node (ref "IC11") (pin "52") (pinfunction "IO_37_52") (pintype "bidirectional"))
    )
    (net (code "102") (name "unconnected-(IC11-IO_42-Pad66)") (class "Default")
      (node (ref "IC11") (pin "66") (pinfunction "IO_42_66") (pintype "bidirectional"))
    )
    (net (code "103") (name "unconnected-(IC11-IO_43-Pad57)") (class "Default")
      (node (ref "IC11") (pin "57") (pinfunction "IO_43_57") (pintype "bidirectional"))
    )
    (net (code "104") (name "unconnected-(IC11-IO_44-Pad67)") (class "Default")
      (node (ref "IC11") (pin "67") (pinfunction "IO_44_67") (pintype "bidirectional"))
    )
    (net (code "105") (name "unconnected-(IC11-IO_46-Pad68)") (class "Default")
      (node (ref "IC11") (pin "68") (pinfunction "IO_46_68") (pintype "bidirectional"))
    )
    (net (code "106") (name "unconnected-(IC11-IO_47-Pad61)") (class "Default")
      (node (ref "IC11") (pin "61") (pinfunction "IO_47_61") (pintype "bidirectional"))
    )
    (net (code "107") (name "unconnected-(IC11-IO_48-Pad69)") (class "Default")
      (node (ref "IC11") (pin "69") (pinfunction "IO_48_69") (pintype "bidirectional"))
    )
    (net (code "108") (name "unconnected-(IC11-IO_49-Pad70)") (class "Default")
      (node (ref "IC11") (pin "70") (pinfunction "IO_49_70") (pintype "bidirectional"))
    )
    (net (code "109") (name "unconnected-(IC11-IO_50-Pad71)") (class "Default")
      (node (ref "IC11") (pin "71") (pinfunction "IO_50_71") (pintype "bidirectional"))
    )
    (net (code "110") (name "unconnected-(IC11-IO_51-Pad72)") (class "Default")
      (node (ref "IC11") (pin "72") (pinfunction "IO_51_72") (pintype "bidirectional"))
    )
    (net (code "111") (name "unconnected-(IC11-IO_52-Pad73)") (class "Default")
      (node (ref "IC11") (pin "73") (pinfunction "IO_52_73") (pintype "bidirectional"))
    )
    (net (code "112") (name "unconnected-(IC11-IO_53-Pad74)") (class "Default")
      (node (ref "IC11") (pin "74") (pinfunction "IO_53_74") (pintype "bidirectional"))
    )
    (net (code "113") (name "unconnected-(IC11-IO_54-Pad75)") (class "Default")
      (node (ref "IC11") (pin "75") (pinfunction "IO_54_75") (pintype "bidirectional"))
    )
    (net (code "114") (name "unconnected-(IC11-IO_55-Pad76)") (class "Default")
      (node (ref "IC11") (pin "76") (pinfunction "IO_55_76") (pintype "bidirectional"))
    )
    (net (code "115") (name "unconnected-(IC11-IO_56-Pad77)") (class "Default")
      (node (ref "IC11") (pin "77") (pinfunction "IO_56_77") (pintype "bidirectional"))
    )
    (net (code "116") (name "unconnected-(IC11-IO_57-Pad78)") (class "Default")
      (node (ref "IC11") (pin "78") (pinfunction "IO_57_78") (pintype "bidirectional"))
    )
    (net (code "117") (name "unconnected-(IC11-IO_58-Pad81)") (class "Default")
      (node (ref "IC11") (pin "81") (pinfunction "IO_58_81") (pintype "bidirectional"))
    )
    (net (code "118") (name "unconnected-(IC11-IO_59-Pad82)") (class "Default")
      (node (ref "IC11") (pin "82") (pinfunction "IO_59_82") (pintype "bidirectional"))
    )
    (net (code "119") (name "unconnected-(IC11-IO_60-Pad83)") (class "Default")
      (node (ref "IC11") (pin "83") (pinfunction "IO_60_83") (pintype "bidirectional"))
    )
    (net (code "120") (name "unconnected-(IC11-IO_61-Pad84)") (class "Default")
      (node (ref "IC11") (pin "84") (pinfunction "IO_61_84") (pintype "bidirectional"))
    )
    (net (code "121") (name "unconnected-(IC11-IO_62-Pad85)") (class "Default")
      (node (ref "IC11") (pin "85") (pinfunction "IO_62_85") (pintype "bidirectional"))
    )
    (net (code "122") (name "unconnected-(IC11-IO_63-Pad86)") (class "Default")
      (node (ref "IC11") (pin "86") (pinfunction "IO_63_86") (pintype "bidirectional"))
    )
    (net (code "123") (name "unconnected-(IC11-IO_64-Pad87)") (class "Default")
      (node (ref "IC11") (pin "87") (pinfunction "IO_64_87") (pintype "bidirectional"))
    )
    (net (code "124") (name "unconnected-(IC11-IO_65-Pad88)") (class "Default")
      (node (ref "IC11") (pin "88") (pinfunction "IO_65_88") (pintype "bidirectional"))
    )
    (net (code "125") (name "unconnected-(IC11-IO_66-Pad89)") (class "Default")
      (node (ref "IC11") (pin "89") (pinfunction "IO_66_89") (pintype "bidirectional"))
    )
    (net (code "126") (name "unconnected-(IC11-IO_67-Pad90)") (class "Default")
      (node (ref "IC11") (pin "90") (pinfunction "IO_67_90") (pintype "bidirectional"))
    )
    (net (code "127") (name "unconnected-(IC11-IO_68-Pad91)") (class "Default")
      (node (ref "IC11") (pin "91") (pinfunction "IO_68_91") (pintype "bidirectional"))
    )
    (net (code "128") (name "unconnected-(IC11-IO_69-Pad92)") (class "Default")
      (node (ref "IC11") (pin "92") (pinfunction "IO_69_92") (pintype "bidirectional"))
    )
    (net (code "129") (name "unconnected-(IC11-IO_70-Pad95)") (class "Default")
      (node (ref "IC11") (pin "95") (pinfunction "IO_70_95") (pintype "bidirectional"))
    )
    (net (code "130") (name "unconnected-(IC11-IO_71-Pad96)") (class "Default")
      (node (ref "IC11") (pin "96") (pinfunction "IO_71_96") (pintype "bidirectional"))
    )
    (net (code "131") (name "unconnected-(IC11-IO_72-Pad97)") (class "Default")
      (node (ref "IC11") (pin "97") (pinfunction "IO_72_97") (pintype "bidirectional"))
    )
    (net (code "132") (name "unconnected-(IC11-IO_73-Pad98)") (class "Default")
      (node (ref "IC11") (pin "98") (pinfunction "IO_73_98") (pintype "bidirectional"))
    )
    (net (code "133") (name "unconnected-(IC11-IO_74-Pad99)") (class "Default")
      (node (ref "IC11") (pin "99") (pinfunction "IO_74_99") (pintype "bidirectional"))
    )
    (net (code "134") (name "unconnected-(IC11-IO{slash}DEV_CLRN-Pad44)") (class "Default")
      (node (ref "IC11") (pin "44") (pinfunction "IO/DEV_CLRN_44") (pintype "bidirectional"))
    )
    (net (code "135") (name "unconnected-(IC11-IO{slash}DEV_OE-Pad43)") (class "Default")
      (node (ref "IC11") (pin "43") (pinfunction "IO/DEV_OE_43") (pintype "bidirectional"))
    )
    (net (code "136") (name "unconnected-(IC11-IO{slash}GCLK2-Pad62)") (class "Default")
      (node (ref "IC11") (pin "62") (pinfunction "IO/GCLK2_62") (pintype "bidirectional"))
    )
    (net (code "137") (name "unconnected-(IC11-IO{slash}GCLK3-Pad64)") (class "Default")
      (node (ref "IC11") (pin "64") (pinfunction "IO/GCLK3_64") (pintype "bidirectional"))
    )
    (net (code "138") (name "unconnected-(QG1-OE-Pad1)") (class "Default")
      (node (ref "QG1") (pin "1") (pinfunction "OE_1") (pintype "input"))
    )
    (net (code "139") (name "unconnected-(SV2-Pad6)") (class "Default")
      (node (ref "SV2") (pin "6") (pinfunction "6_6") (pintype "passive"))
    )
    (net (code "140") (name "unconnected-(SV2-Pad7)") (class "Default")
      (node (ref "SV2") (pin "7") (pinfunction "7_7") (pintype "passive"))
    )
    (net (code "141") (name "unconnected-(SV2-Pad8)") (class "Default")
      (node (ref "SV2") (pin "8") (pinfunction "8_8") (pintype "passive"))
    )
  )
)
